# sb-sonata-usbrp.net
KiCad netlist of a schematic drawn in Altium Designer
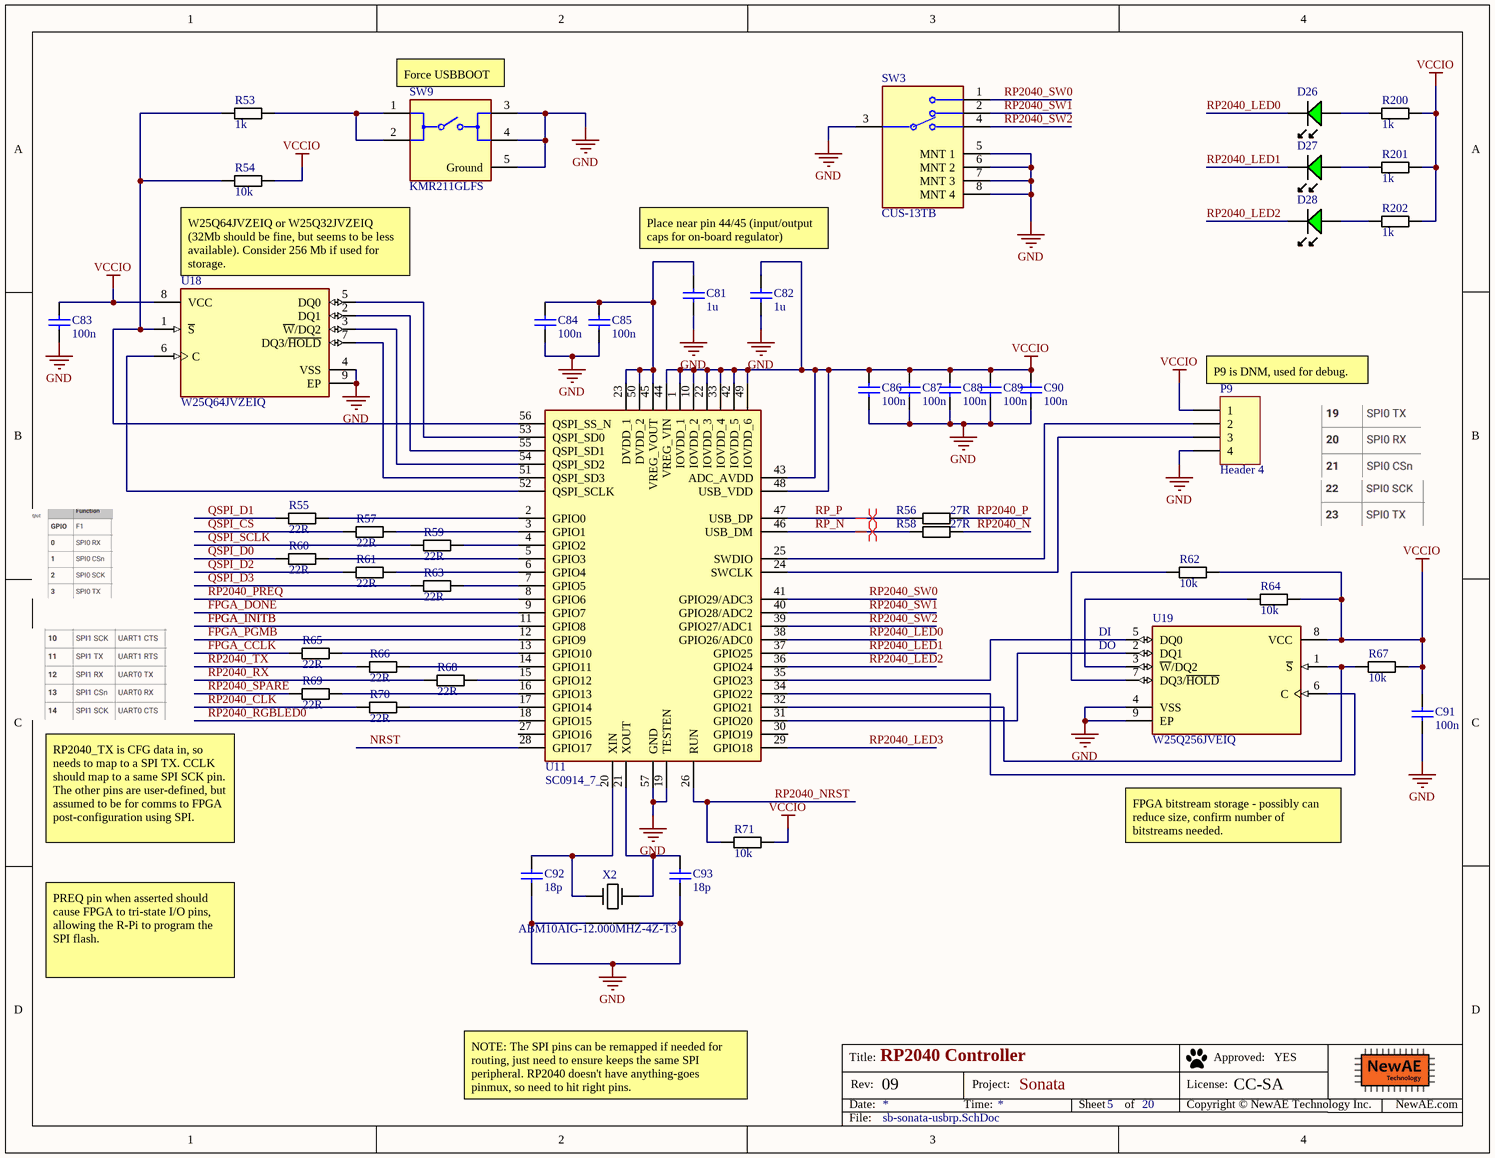
[diagram p0: sb-sonata-usbrp.SchDoc]

(export (version "E")
  (design (tool "Eeschema 10.0.6"))
  (components
    (comp (ref "C81")
      (value "1u")
      (footprint "CAPC0603_M")
      (description "1u, 0603, 50V")
      (fields (field (name "PART NUMBER") "CCHIP-1u-0603"))
      (libsource (lib "NewAE_AltiumLib") (part "CAP"))
    )
    (comp (ref "C82")
      (value "1u")
      (footprint "CAPC0603_M")
      (description "1u, 0603, 50V")
      (fields (field (name "PART NUMBER") "CCHIP-1u-0603"))
      (libsource (lib "NewAE_AltiumLib") (part "CAP"))
    )
    (comp (ref "C83")
      (value "100n")
      (footprint "CAPC0402_M")
      (description "100n, 0402")
      (fields (field (name "PART NUMBER") "CCHIP-100n-0402"))
      (libsource (lib "NewAE_AltiumLib") (part "CAP"))
    )
    (comp (ref "C84")
      (value "100n")
      (footprint "CAPC0402_M")
      (description "100n, 0402")
      (fields (field (name "PART NUMBER") "CCHIP-100n-0402"))
      (libsource (lib "NewAE_AltiumLib") (part "CAP"))
    )
    (comp (ref "C85")
      (value "100n")
      (footprint "CAPC0402_M")
      (description "100n, 0402")
      (fields (field (name "PART NUMBER") "CCHIP-100n-0402"))
      (libsource (lib "NewAE_AltiumLib") (part "CAP"))
    )
    (comp (ref "C86")
      (value "100n")
      (footprint "CAPC0402_M")
      (description "100n, 0402")
      (fields (field (name "PART NUMBER") "CCHIP-100n-0402"))
      (libsource (lib "NewAE_AltiumLib") (part "CAP"))
    )
    (comp (ref "C87")
      (value "100n")
      (footprint "CAPC0402_M")
      (description "100n, 0402")
      (fields (field (name "PART NUMBER") "CCHIP-100n-0402"))
      (libsource (lib "NewAE_AltiumLib") (part "CAP"))
    )
    (comp (ref "C88")
      (value "100n")
      (footprint "CAPC0402_M")
      (description "100n, 0402")
      (fields (field (name "PART NUMBER") "CCHIP-100n-0402"))
      (libsource (lib "NewAE_AltiumLib") (part "CAP"))
    )
    (comp (ref "C89")
      (value "100n")
      (footprint "CAPC0402_M")
      (description "100n, 0402")
      (fields (field (name "PART NUMBER") "CCHIP-100n-0402"))
      (libsource (lib "NewAE_AltiumLib") (part "CAP"))
    )
    (comp (ref "C90")
      (value "100n")
      (footprint "CAPC0402_M")
      (description "100n, 0402")
      (fields (field (name "PART NUMBER") "CCHIP-100n-0402"))
      (libsource (lib "NewAE_AltiumLib") (part "CAP"))
    )
    (comp (ref "C91")
      (value "100n")
      (footprint "CAPC0402_M")
      (description "100n, 0402")
      (fields (field (name "PART NUMBER") "CCHIP-100n-0402"))
      (libsource (lib "NewAE_AltiumLib") (part "CAP"))
    )
    (comp (ref "C92")
      (value "18p")
      (footprint "CAPC0402_M")
      (description "18p, 0402")
      (fields (field (name "PART NUMBER") "CCHIP-18p-0402"))
      (libsource (lib "NewAE_AltiumLib") (part "CAP"))
    )
    (comp (ref "C93")
      (value "18p")
      (footprint "CAPC0402_M")
      (description "18p, 0402")
      (fields (field (name "PART NUMBER") "CCHIP-18p-0402"))
      (libsource (lib "NewAE_AltiumLib") (part "CAP"))
    )
    (comp (ref "D26")
      (value "LED, 0603, Green")
      (footprint "LED-0603-GREEN")
      (description "Chip LED, Green")
      (fields (field (name "PART NUMBER") "LEDCHIP_0603_GREEN"))
      (libsource (lib "NewAE_AltiumLib") (part "LED_GREEN"))
    )
    (comp (ref "D27")
      (value "LED, 0603, Green")
      (footprint "LED-0603-GREEN")
      (description "Chip LED, Green")
      (fields (field (name "PART NUMBER") "LEDCHIP_0603_GREEN"))
      (libsource (lib "NewAE_AltiumLib") (part "LED_GREEN"))
    )
    (comp (ref "D28")
      (value "LED, 0603, Green")
      (footprint "LED-0603-GREEN")
      (description "Chip LED, Green")
      (fields (field (name "PART NUMBER") "LEDCHIP_0603_GREEN"))
      (libsource (lib "NewAE_AltiumLib") (part "LED_GREEN"))
    )
    (comp (ref "P9")
      (value "Header 4")
      (footprint "HDR1X4")
      (description "Header, 4-Pin")
      (fields (field (name "PUBLISHER") "Altium Limited"))
      (libsource (lib "Miscellaneous Connectors") (part "Header 4"))
    )
    (comp (ref "R53")
      (value "1k")
      (footprint "RESC1005X40N")
      (description "1k res, 0402, 1%, 1/16W")
      (fields (field (name "PART NUMBER") "RCHIP-1K-0402") (field (name "TOLERANCE") "1%"))
      (libsource (lib "") (part "RES-EU_1"))
    )
    (comp (ref "R54")
      (value "10k")
      (footprint "RESC1005X40N")
      (description "10k res, 0402, 1%, 1/16W")
      (fields (field (name "PART NUMBER") "RCHIP-10K-0402") (field (name "TOLERANCE") "1%"))
      (libsource (lib "NewAE_AltiumLib") (part "RES-EU"))
    )
    (comp (ref "R55")
      (value "22R")
      (footprint "RESC1005X40N")
      (description "22R res, 0402, 1%, 1/16W")
      (fields (field (name "PART NUMBER") "RCHIP-22R-0402") (field (name "TOLERANCE") "1%"))
      (libsource (lib "") (part "RES-EU_1"))
    )
    (comp (ref "R56")
      (value "27R")
      (footprint "RESC1005X40N")
      (description "27R res, 0402, 1%, 1/16W")
      (fields (field (name "PART NUMBER") "RCHIP-27R-0402") (field (name "TOLERANCE") "1%"))
      (libsource (lib "NewAE_AltiumLib") (part "RES-EU"))
    )
    (comp (ref "R57")
      (value "22R")
      (footprint "RESC1005X40N")
      (description "22R res, 0402, 1%, 1/16W")
      (fields (field (name "PART NUMBER") "RCHIP-22R-0402") (field (name "TOLERANCE") "1%"))
      (libsource (lib "") (part "RES-EU_1"))
    )
    (comp (ref "R58")
      (value "27R")
      (footprint "RESC1005X40N")
      (description "27R res, 0402, 1%, 1/16W")
      (fields (field (name "PART NUMBER") "RCHIP-27R-0402") (field (name "TOLERANCE") "1%"))
      (libsource (lib "NewAE_AltiumLib") (part "RES-EU"))
    )
    (comp (ref "R59")
      (value "22R")
      (footprint "RESC1005X40N")
      (description "22R res, 0402, 1%, 1/16W")
      (fields (field (name "PART NUMBER") "RCHIP-22R-0402") (field (name "TOLERANCE") "1%"))
      (libsource (lib "") (part "RES-EU_1"))
    )
    (comp (ref "R60")
      (value "22R")
      (footprint "RESC1005X40N")
      (description "22R res, 0402, 1%, 1/16W")
      (fields (field (name "PART NUMBER") "RCHIP-22R-0402") (field (name "TOLERANCE") "1%"))
      (libsource (lib "") (part "RES-EU_1"))
    )
    (comp (ref "R61")
      (value "22R")
      (footprint "RESC1005X40N")
      (description "22R res, 0402, 1%, 1/16W")
      (fields (field (name "PART NUMBER") "RCHIP-22R-0402") (field (name "TOLERANCE") "1%"))
      (libsource (lib "") (part "RES-EU_1"))
    )
    (comp (ref "R62")
      (value "10k")
      (footprint "RESC1005X40N")
      (description "10k res, 0402, 1%, 1/16W")
      (fields (field (name "PART NUMBER") "RCHIP-10K-0402") (field (name "TOLERANCE") "1%"))
      (libsource (lib "NewAE_AltiumLib") (part "RES-EU"))
    )
    (comp (ref "R63")
      (value "22R")
      (footprint "RESC1005X40N")
      (description "22R res, 0402, 1%, 1/16W")
      (fields (field (name "PART NUMBER") "RCHIP-22R-0402") (field (name "TOLERANCE") "1%"))
      (libsource (lib "") (part "RES-EU_1"))
    )
    (comp (ref "R64")
      (value "10k")
      (footprint "RESC1005X40N")
      (description "10k res, 0402, 1%, 1/16W")
      (fields (field (name "PART NUMBER") "RCHIP-10K-0402") (field (name "TOLERANCE") "1%"))
      (libsource (lib "NewAE_AltiumLib") (part "RES-EU"))
    )
    (comp (ref "R65")
      (value "22R")
      (footprint "RESC1005X40N")
      (description "22R res, 0402, 1%, 1/16W")
      (fields (field (name "PART NUMBER") "RCHIP-22R-0402") (field (name "TOLERANCE") "1%"))
      (libsource (lib "") (part "RES-EU_1"))
    )
    (comp (ref "R66")
      (value "22R")
      (footprint "RESC1005X40N")
      (description "22R res, 0402, 1%, 1/16W")
      (fields (field (name "PART NUMBER") "RCHIP-22R-0402") (field (name "TOLERANCE") "1%"))
      (libsource (lib "") (part "RES-EU_1"))
    )
    (comp (ref "R67")
      (value "10k")
      (footprint "RESC1005X40N")
      (description "10k res, 0402, 1%, 1/16W")
      (fields (field (name "PART NUMBER") "RCHIP-10K-0402") (field (name "TOLERANCE") "1%"))
      (libsource (lib "") (part "RES-EU_1"))
    )
    (comp (ref "R68")
      (value "22R")
      (footprint "RESC1005X40N")
      (description "22R res, 0402, 1%, 1/16W")
      (fields (field (name "PART NUMBER") "RCHIP-22R-0402") (field (name "TOLERANCE") "1%"))
      (libsource (lib "") (part "RES-EU_1"))
    )
    (comp (ref "R69")
      (value "22R")
      (footprint "RESC1005X40N")
      (description "22R res, 0402, 1%, 1/16W")
      (fields (field (name "PART NUMBER") "RCHIP-22R-0402") (field (name "TOLERANCE") "1%"))
      (libsource (lib "") (part "RES-EU_1"))
    )
    (comp (ref "R70")
      (value "22R")
      (footprint "RESC1005X40N")
      (description "22R res, 0402, 1%, 1/16W")
      (fields (field (name "PART NUMBER") "RCHIP-22R-0402") (field (name "TOLERANCE") "1%"))
      (libsource (lib "") (part "RES-EU_1"))
    )
    (comp (ref "R71")
      (value "10k")
      (footprint "RESC1005X40N")
      (description "10k res, 0402, 1%, 1/16W")
      (fields (field (name "PART NUMBER") "RCHIP-10K-0402") (field (name "TOLERANCE") "1%"))
      (libsource (lib "") (part "RES-EU_1"))
    )
    (comp (ref "R200")
      (value "1k")
      (footprint "RESC1005X40N")
      (description "1k res, 0402, 1%, 1/16W")
      (fields (field (name "PART NUMBER") "RCHIP-1K-0402") (field (name "TOLERANCE") "1%"))
      (libsource (lib "") (part "RES-EU_1"))
    )
    (comp (ref "R201")
      (value "1k")
      (footprint "RESC1005X40N")
      (description "1k res, 0402, 1%, 1/16W")
      (fields (field (name "PART NUMBER") "RCHIP-1K-0402") (field (name "TOLERANCE") "1%"))
      (libsource (lib "") (part "RES-EU_1"))
    )
    (comp (ref "R202")
      (value "1k")
      (footprint "RESC1005X40N")
      (description "1k res, 0402, 1%, 1/16W")
      (fields (field (name "PART NUMBER") "RCHIP-1K-0402") (field (name "TOLERANCE") "1%"))
      (libsource (lib "") (part "RES-EU_1"))
    )
    (comp (ref "SW3")
      (value "CUS-13TB")
      (footprint "FP-CUS-13TB-MFG")
      (description "SWITCH SLIDE SP3T 300MA 4V")
      (libsource (lib "Altium Content Vault") (part "47bcb96ef67674530f45e4053201745"))
    )
    (comp (ref "SW9")
      (value "KMR211GLFS")
      (footprint "FP-KMR211GLFS-MFG")
      (description "SWITCH TACTILE SPST-NO 0.05A 32V")
      (libsource (lib "Altium Content Vault") (part "99988cc0f9d3d39bd794ae22da860e5"))
    )
    (comp (ref "U11")
      (value "SC0914_7_")
      (footprint "QFN40P700X700X90-57N-D")
      (description "Connector")
      (fields
        (field (name "MANUFACTURER_PART_NUMBER") "SC0914(7)")
        (field (name "MOUSER PART NUMBER") "358-SC09147")
      )
      (libsource (lib "*") (part "SC0914_7_"))
    )
    (comp (ref "U18")
      (value "W25Q64JVZEIQ")
      (footprint "WSON68_Micron")
      (description "IC FLASH 64M SPI 133MHZ 8WPDFN")
      (libsource (lib "NewAE_AltiumLib") (part "QSPI_WSON"))
    )
    (comp (ref "U19")
      (value "W25Q256JVEIQ")
      (footprint "WSON68_Micron")
      (description "IC FLASH 256M SPI 133MHZ 8WPDFN")
      (libsource (lib "") (part "QSPI_WSON_1"))
    )
    (comp (ref "X2")
      (value "ABM10AIG-12.000MHZ-4Z-T3")
      (footprint "2.5x2mm XTAL")
      (description "12MHz, SMD")
      (libsource (lib "NewAE_AltiumLib") (part "XTAL_4PIN_13"))
    )
  )
  (nets
    (net (code "1") (name "/FPGA_CCLK") (class "Default")
      (node (ref "R65") (pin "1") (pinfunction "1_1") (pintype "passive"))
    )
    (net (code "2") (name "/FPGA_DONE") (class "Default")
      (node (ref "U11") (pin "9") (pinfunction "GPIO7_9") (pintype "passive"))
    )
    (net (code "3") (name "/FPGA_INITB") (class "Default")
      (node (ref "U11") (pin "11") (pinfunction "GPIO8_11") (pintype "passive"))
    )
    (net (code "4") (name "/FPGA_PGMB") (class "Default")
      (node (ref "U11") (pin "12") (pinfunction "GPIO9_12") (pintype "passive"))
    )
    (net (code "5") (name "/NRST") (class "Default")
      (node (ref "U11") (pin "28") (pinfunction "GPIO17_28") (pintype "passive"))
    )
    (net (code "6") (name "/QSPI_CS") (class "Default")
      (node (ref "R57") (pin "1") (pinfunction "1_1") (pintype "passive"))
    )
    (net (code "7") (name "/QSPI_D0") (class "Default")
      (node (ref "R60") (pin "1") (pinfunction "1_1") (pintype "passive"))
    )
    (net (code "8") (name "/QSPI_D1") (class "Default")
      (node (ref "R55") (pin "1") (pinfunction "1_1") (pintype "passive"))
    )
    (net (code "9") (name "/QSPI_D2") (class "Default")
      (node (ref "R61") (pin "1") (pinfunction "1_1") (pintype "passive"))
    )
    (net (code "10") (name "/QSPI_D3") (class "Default")
      (node (ref "R63") (pin "1") (pinfunction "1_1") (pintype "passive"))
    )
    (net (code "11") (name "/QSPI_SCLK") (class "Default")
      (node (ref "R59") (pin "1") (pinfunction "1_1") (pintype "passive"))
    )
    (net (code "12") (name "/RP2040_CLK") (class "Default")
      (node (ref "R70") (pin "1") (pinfunction "1_1") (pintype "passive"))
    )
    (net (code "13") (name "/RP2040_LED0") (class "Default")
      (node (ref "D26") (pin "K") (pinfunction "K_K") (pintype "passive"))
      (node (ref "U11") (pin "38") (pinfunction "GPIO26/ADC0_38") (pintype "passive"))
    )
    (net (code "14") (name "/RP2040_LED1") (class "Default")
      (node (ref "D27") (pin "K") (pinfunction "K_K") (pintype "passive"))
      (node (ref "U11") (pin "37") (pinfunction "GPIO25_37") (pintype "passive"))
    )
    (net (code "15") (name "/RP2040_LED2") (class "Default")
      (node (ref "D28") (pin "K") (pinfunction "K_K") (pintype "passive"))
      (node (ref "U11") (pin "36") (pinfunction "GPIO24_36") (pintype "passive"))
    )
    (net (code "16") (name "/RP2040_LED3") (class "Default")
      (node (ref "U11") (pin "29") (pinfunction "GPIO18_29") (pintype "passive"))
    )
    (net (code "17") (name "/RP2040_N") (class "Default")
      (node (ref "R58") (pin "1") (pinfunction "1_1") (pintype "passive"))
    )
    (net (code "18") (name "/RP2040_NRST") (class "Default")
      (node (ref "R71") (pin "1") (pinfunction "1_1") (pintype "passive"))
      (node (ref "U11") (pin "26") (pinfunction "RUN_26") (pintype "passive"))
    )
    (net (code "19") (name "/RP2040_P") (class "Default")
      (node (ref "R56") (pin "1") (pinfunction "1_1") (pintype "passive"))
    )
    (net (code "20") (name "/RP2040_PREQ") (class "Default")
      (node (ref "U11") (pin "8") (pinfunction "GPIO6_8") (pintype "passive"))
    )
    (net (code "21") (name "/RP2040_RGBLED0") (class "Default")
      (node (ref "U11") (pin "18") (pinfunction "GPIO15_18") (pintype "passive"))
    )
    (net (code "22") (name "/RP2040_RX") (class "Default")
      (node (ref "R68") (pin "1") (pinfunction "1_1") (pintype "passive"))
    )
    (net (code "23") (name "/RP2040_SPARE") (class "Default")
      (node (ref "R69") (pin "1") (pinfunction "1_1") (pintype "passive"))
    )
    (net (code "24") (name "/RP2040_SW0") (class "Default")
      (node (ref "SW3") (pin "1") (pinfunction "1_1") (pintype "passive"))
      (node (ref "U11") (pin "41") (pinfunction "GPIO29/ADC3_41") (pintype "passive"))
    )
    (net (code "25") (name "/RP2040_SW1") (class "Default")
      (node (ref "SW3") (pin "2") (pinfunction "2_2") (pintype "passive"))
      (node (ref "U11") (pin "40") (pinfunction "GPIO28/ADC2_40") (pintype "passive"))
    )
    (net (code "26") (name "/RP2040_SW2") (class "Default")
      (node (ref "SW3") (pin "4") (pinfunction "4_4") (pintype "passive"))
      (node (ref "U11") (pin "39") (pinfunction "GPIO27/ADC1_39") (pintype "passive"))
    )
    (net (code "27") (name "/RP2040_TX") (class "Default")
      (node (ref "R66") (pin "1") (pinfunction "1_1") (pintype "passive"))
    )
    (net (code "28") (name "/RP_N") (class "Default")
      (node (ref "R58") (pin "2") (pinfunction "2_2") (pintype "passive"))
      (node (ref "U11") (pin "46") (pinfunction "USB_DM_46") (pintype "passive"))
    )
    (net (code "29") (name "/RP_P") (class "Default")
      (node (ref "R56") (pin "2") (pinfunction "2_2") (pintype "passive"))
      (node (ref "U11") (pin "47") (pinfunction "USB_DP_47") (pintype "passive"))
    )
    (net (code "30") (name "GND") (class "Default")
      (node (ref "C81") (pin "2") (pinfunction "2_2") (pintype "passive"))
      (node (ref "C82") (pin "2") (pinfunction "2_2") (pintype "passive"))
      (node (ref "C83") (pin "2") (pinfunction "2_2") (pintype "passive"))
      (node (ref "C84") (pin "2") (pinfunction "2_2") (pintype "passive"))
      (node (ref "C85") (pin "2") (pinfunction "2_2") (pintype "passive"))
      (node (ref "C86") (pin "2") (pinfunction "2_2") (pintype "passive"))
      (node (ref "C87") (pin "2") (pinfunction "2_2") (pintype "passive"))
      (node (ref "C88") (pin "2") (pinfunction "2_2") (pintype "passive"))
      (node (ref "C89") (pin "2") (pinfunction "2_2") (pintype "passive"))
      (node (ref "C90") (pin "2") (pinfunction "2_2") (pintype "passive"))
      (node (ref "C91") (pin "2") (pinfunction "2_2") (pintype "passive"))
      (node (ref "C92") (pin "2") (pinfunction "2_2") (pintype "passive"))
      (node (ref "C93") (pin "2") (pinfunction "2_2") (pintype "passive"))
      (node (ref "P9") (pin "4") (pinfunction "4_4") (pintype "passive"))
      (node (ref "SW3") (pin "3") (pinfunction "C_3") (pintype "passive"))
      (node (ref "SW3") (pin "5") (pinfunction "MNT_1_5") (pintype "passive"))
      (node (ref "SW3") (pin "6") (pinfunction "MNT_2_6") (pintype "passive"))
      (node (ref "SW3") (pin "7") (pinfunction "MNT_3_7") (pintype "passive"))
      (node (ref "SW3") (pin "8") (pinfunction "MNT_4_8") (pintype "passive"))
      (node (ref "SW9") (pin "3") (pinfunction "3_3") (pintype "passive"))
      (node (ref "SW9") (pin "4") (pinfunction "4_4") (pintype "passive"))
      (node (ref "SW9") (pin "5") (pinfunction "Ground_5") (pintype "power_in"))
      (node (ref "U11") (pin "19") (pinfunction "TESTEN_19") (pintype "passive"))
      (node (ref "U11") (pin "57") (pinfunction "GND_57") (pintype "passive"))
      (node (ref "U18") (pin "4") (pinfunction "VSS_4") (pintype "power_in"))
      (node (ref "U18") (pin "9") (pinfunction "EP_9") (pintype "power_in"))
      (node (ref "U19") (pin "4") (pinfunction "VSS_4") (pintype "power_in"))
      (node (ref "U19") (pin "9") (pinfunction "EP_9") (pintype "power_in"))
      (node (ref "X2") (pin "2") (pinfunction "GND_2") (pintype "power_in"))
      (node (ref "X2") (pin "4") (pinfunction "GND_4") (pintype "power_in"))
    )
    (net (code "31") (name "Net-(D26-PadA)") (class "Default")
      (node (ref "D26") (pin "A") (pinfunction "A_A") (pintype "passive"))
      (node (ref "R200") (pin "1") (pinfunction "1_1") (pintype "passive"))
    )
    (net (code "32") (name "Net-(D27-PadA)") (class "Default")
      (node (ref "D27") (pin "A") (pinfunction "A_A") (pintype "passive"))
      (node (ref "R201") (pin "1") (pinfunction "1_1") (pintype "passive"))
    )
    (net (code "33") (name "Net-(D28-PadA)") (class "Default")
      (node (ref "D28") (pin "A") (pinfunction "A_A") (pintype "passive"))
      (node (ref "R202") (pin "1") (pinfunction "1_1") (pintype "passive"))
    )
    (net (code "34") (name "Net-(R53-Pad2)") (class "Default")
      (node (ref "R53") (pin "2") (pinfunction "2_2") (pintype "passive"))
      (node (ref "SW9") (pin "1") (pinfunction "1_1") (pintype "passive"))
      (node (ref "SW9") (pin "2") (pinfunction "2_2") (pintype "passive"))
    )
    (net (code "35") (name "Net-(U11-DVDD_1)") (class "Default")
      (node (ref "C81") (pin "1") (pinfunction "1_1") (pintype "passive"))
      (node (ref "C84") (pin "1") (pinfunction "1_1") (pintype "passive"))
      (node (ref "C85") (pin "1") (pinfunction "1_1") (pintype "passive"))
      (node (ref "U11") (pin "23") (pinfunction "DVDD_1_23") (pintype "passive"))
      (node (ref "U11") (pin "45") (pinfunction "VREG_VOUT_45") (pintype "passive"))
      (node (ref "U11") (pin "50") (pinfunction "DVDD_2_50") (pintype "passive"))
    )
    (net (code "36") (name "Net-(U11-GPIO0)") (class "Default")
      (node (ref "R55") (pin "2") (pinfunction "2_2") (pintype "passive"))
      (node (ref "U11") (pin "2") (pinfunction "GPIO0_2") (pintype "passive"))
    )
    (net (code "37") (name "Net-(U11-GPIO1)") (class "Default")
      (node (ref "R57") (pin "2") (pinfunction "2_2") (pintype "passive"))
      (node (ref "U11") (pin "3") (pinfunction "GPIO1_3") (pintype "passive"))
    )
    (net (code "38") (name "Net-(U11-GPIO2)") (class "Default")
      (node (ref "R59") (pin "2") (pinfunction "2_2") (pintype "passive"))
      (node (ref "U11") (pin "4") (pinfunction "GPIO2_4") (pintype "passive"))
    )
    (net (code "39") (name "Net-(U11-GPIO3)") (class "Default")
      (node (ref "R60") (pin "2") (pinfunction "2_2") (pintype "passive"))
      (node (ref "U11") (pin "5") (pinfunction "GPIO3_5") (pintype "passive"))
    )
    (net (code "40") (name "Net-(U11-GPIO4)") (class "Default")
      (node (ref "R61") (pin "2") (pinfunction "2_2") (pintype "passive"))
      (node (ref "U11") (pin "6") (pinfunction "GPIO4_6") (pintype "passive"))
    )
    (net (code "41") (name "Net-(U11-GPIO5)") (class "Default")
      (node (ref "R63") (pin "2") (pinfunction "2_2") (pintype "passive"))
      (node (ref "U11") (pin "7") (pinfunction "GPIO5_7") (pintype "passive"))
    )
    (net (code "42") (name "Net-(U11-GPIO10)") (class "Default")
      (node (ref "R65") (pin "2") (pinfunction "2_2") (pintype "passive"))
      (node (ref "U11") (pin "13") (pinfunction "GPIO10_13") (pintype "passive"))
    )
    (net (code "43") (name "Net-(U11-GPIO11)") (class "Default")
      (node (ref "R66") (pin "2") (pinfunction "2_2") (pintype "passive"))
      (node (ref "U11") (pin "14") (pinfunction "GPIO11_14") (pintype "passive"))
    )
    (net (code "44") (name "Net-(U11-GPIO12)") (class "Default")
      (node (ref "R68") (pin "2") (pinfunction "2_2") (pintype "passive"))
      (node (ref "U11") (pin "15") (pinfunction "GPIO12_15") (pintype "passive"))
    )
    (net (code "45") (name "Net-(U11-GPIO13)") (class "Default")
      (node (ref "R69") (pin "2") (pinfunction "2_2") (pintype "passive"))
      (node (ref "U11") (pin "16") (pinfunction "GPIO13_16") (pintype "passive"))
    )
    (net (code "46") (name "Net-(U11-GPIO14)") (class "Default")
      (node (ref "R70") (pin "2") (pinfunction "2_2") (pintype "passive"))
      (node (ref "U11") (pin "17") (pinfunction "GPIO14_17") (pintype "passive"))
    )
    (net (code "47") (name "Net-(U11-GPIO20)") (class "Default")
      (node (ref "U11") (pin "31") (pinfunction "GPIO20_31") (pintype "passive"))
      (node (ref "U19") (pin "2") (pinfunction "DQ1_2") (pintype "bidirectional"))
    )
    (net (code "48") (name "Net-(U11-GPIO21)") (class "Default")
      (node (ref "R67") (pin "1") (pinfunction "1_1") (pintype "passive"))
      (node (ref "U11") (pin "32") (pinfunction "GPIO21_32") (pintype "passive"))
      (node (ref "U19") (pin "1") (pinfunction "~{S}_1") (pintype "input"))
    )
    (net (code "49") (name "Net-(U11-GPIO22)") (class "Default")
      (node (ref "U11") (pin "34") (pinfunction "GPIO22_34") (pintype "passive"))
      (node (ref "U19") (pin "6") (pinfunction "C_6") (pintype "input"))
    )
    (net (code "50") (name "Net-(U11-GPIO23)") (class "Default")
      (node (ref "U11") (pin "35") (pinfunction "GPIO23_35") (pintype "passive"))
      (node (ref "U19") (pin "5") (pinfunction "DQ0_5") (pintype "bidirectional"))
    )
    (net (code "51") (name "Net-(U11-QSPI_SCLK)") (class "Default")
      (node (ref "U11") (pin "52") (pinfunction "QSPI_SCLK_52") (pintype "passive"))
      (node (ref "U18") (pin "6") (pinfunction "C_6") (pintype "input"))
    )
    (net (code "52") (name "Net-(U11-QSPI_SD0)") (class "Default")
      (node (ref "U11") (pin "53") (pinfunction "QSPI_SD0_53") (pintype "passive"))
      (node (ref "U18") (pin "5") (pinfunction "DQ0_5") (pintype "bidirectional"))
    )
    (net (code "53") (name "Net-(U11-QSPI_SD1)") (class "Default")
      (node (ref "U11") (pin "55") (pinfunction "QSPI_SD1_55") (pintype "passive"))
      (node (ref "U18") (pin "2") (pinfunction "DQ1_2") (pintype "bidirectional"))
    )
    (net (code "54") (name "Net-(U11-QSPI_SD2)") (class "Default")
      (node (ref "U11") (pin "54") (pinfunction "QSPI_SD2_54") (pintype "passive"))
      (node (ref "U18") (pin "3") (pinfunction "~{W}/DQ2_3") (pintype "bidirectional"))
    )
    (net (code "55") (name "Net-(U11-QSPI_SD3)") (class "Default")
      (node (ref "U11") (pin "51") (pinfunction "QSPI_SD3_51") (pintype "passive"))
      (node (ref "U18") (pin "7") (pinfunction "DQ3/~{HOLD}_7") (pintype "bidirectional"))
    )
    (net (code "56") (name "Net-(U11-QSPI_SS_N)") (class "Default")
      (node (ref "R53") (pin "1") (pinfunction "1_1") (pintype "passive"))
      (node (ref "R54") (pin "2") (pinfunction "2_2") (pintype "passive"))
      (node (ref "U11") (pin "56") (pinfunction "QSPI_SS_N_56") (pintype "passive"))
      (node (ref "U18") (pin "1") (pinfunction "~{S}_1") (pintype "input"))
    )
    (net (code "57") (name "Net-(U11-SWCLK)") (class "Default")
      (node (ref "P9") (pin "3") (pinfunction "3_3") (pintype "passive"))
      (node (ref "U11") (pin "24") (pinfunction "SWCLK_24") (pintype "passive"))
    )
    (net (code "58") (name "Net-(U11-SWDIO)") (class "Default")
      (node (ref "P9") (pin "2") (pinfunction "2_2") (pintype "passive"))
      (node (ref "U11") (pin "25") (pinfunction "SWDIO_25") (pintype "passive"))
    )
    (net (code "59") (name "Net-(U11-XIN)") (class "Default")
      (node (ref "C92") (pin "1") (pinfunction "1_1") (pintype "passive"))
      (node (ref "U11") (pin "20") (pinfunction "XIN_20") (pintype "passive"))
      (node (ref "X2") (pin "1") (pinfunction "IN_1") (pintype "passive"))
    )
    (net (code "60") (name "Net-(U11-XOUT)") (class "Default")
      (node (ref "C93") (pin "1") (pinfunction "1_1") (pintype "passive"))
      (node (ref "U11") (pin "21") (pinfunction "XOUT_21") (pintype "passive"))
      (node (ref "X2") (pin "3") (pinfunction "OUT_3") (pintype "passive"))
    )
    (net (code "61") (name "Net-(U19-DQ3{slash}~{HOLD})") (class "Default")
      (node (ref "R62") (pin "2") (pinfunction "2_2") (pintype "passive"))
      (node (ref "U19") (pin "7") (pinfunction "DQ3/~{HOLD}_7") (pintype "bidirectional"))
    )
    (net (code "62") (name "Net-(U19-~{W}{slash}DQ2)") (class "Default")
      (node (ref "R64") (pin "2") (pinfunction "2_2") (pintype "passive"))
      (node (ref "U19") (pin "3") (pinfunction "~{W}/DQ2_3") (pintype "bidirectional"))
    )
    (net (code "63") (name "VCCIO") (class "Default")
      (node (ref "C82") (pin "1") (pinfunction "1_1") (pintype "passive"))
      (node (ref "C83") (pin "1") (pinfunction "1_1") (pintype "passive"))
      (node (ref "C86") (pin "1") (pinfunction "1_1") (pintype "passive"))
      (node (ref "C87") (pin "1") (pinfunction "1_1") (pintype "passive"))
      (node (ref "C88") (pin "1") (pinfunction "1_1") (pintype "passive"))
      (node (ref "C89") (pin "1") (pinfunction "1_1") (pintype "passive"))
      (node (ref "C90") (pin "1") (pinfunction "1_1") (pintype "passive"))
      (node (ref "C91") (pin "1") (pinfunction "1_1") (pintype "passive"))
      (node (ref "P9") (pin "1") (pinfunction "1_1") (pintype "passive"))
      (node (ref "R200") (pin "2") (pinfunction "2_2") (pintype "passive"))
      (node (ref "R201") (pin "2") (pinfunction "2_2") (pintype "passive"))
      (node (ref "R202") (pin "2") (pinfunction "2_2") (pintype "passive"))
      (node (ref "R54") (pin "1") (pinfunction "1_1") (pintype "passive"))
      (node (ref "R62") (pin "1") (pinfunction "1_1") (pintype "passive"))
      (node (ref "R64") (pin "1") (pinfunction "1_1") (pintype "passive"))
      (node (ref "R67") (pin "2") (pinfunction "2_2") (pintype "passive"))
      (node (ref "R71") (pin "2") (pinfunction "2_2") (pintype "passive"))
      (node (ref "U11") (pin "1") (pinfunction "IOVDD_1_1") (pintype "passive"))
      (node (ref "U11") (pin "10") (pinfunction "IOVDD_2_10") (pintype "passive"))
      (node (ref "U11") (pin "22") (pinfunction "IOVDD_3_22") (pintype "passive"))
      (node (ref "U11") (pin "33") (pinfunction "IOVDD_4_33") (pintype "passive"))
      (node (ref "U11") (pin "42") (pinfunction "IOVDD_5_42") (pintype "passive"))
      (node (ref "U11") (pin "43") (pinfunction "ADC_AVDD_43") (pintype "passive"))
      (node (ref "U11") (pin "44") (pinfunction "VREG_VIN_44") (pintype "passive"))
      (node (ref "U11") (pin "48") (pinfunction "USB_VDD_48") (pintype "passive"))
      (node (ref "U11") (pin "49") (pinfunction "IOVDD_6_49") (pintype "passive"))
      (node (ref "U18") (pin "8") (pinfunction "VCC_8") (pintype "power_in"))
      (node (ref "U19") (pin "8") (pinfunction "VCC_8") (pintype "power_in"))
    )
    (net (code "64") (name "unconnected-(U11-GPIO16-Pad27)") (class "Default")
      (node (ref "U11") (pin "27") (pinfunction "GPIO16_27") (pintype "passive"))
    )
    (net (code "65") (name "unconnected-(U11-GPIO19-Pad30)") (class "Default")
      (node (ref "U11") (pin "30") (pinfunction "GPIO19_30") (pintype "passive"))
    )
  )
)
